# LICL_Amplifier.net
KiCad netlist of a schematic drawn in EAGLE
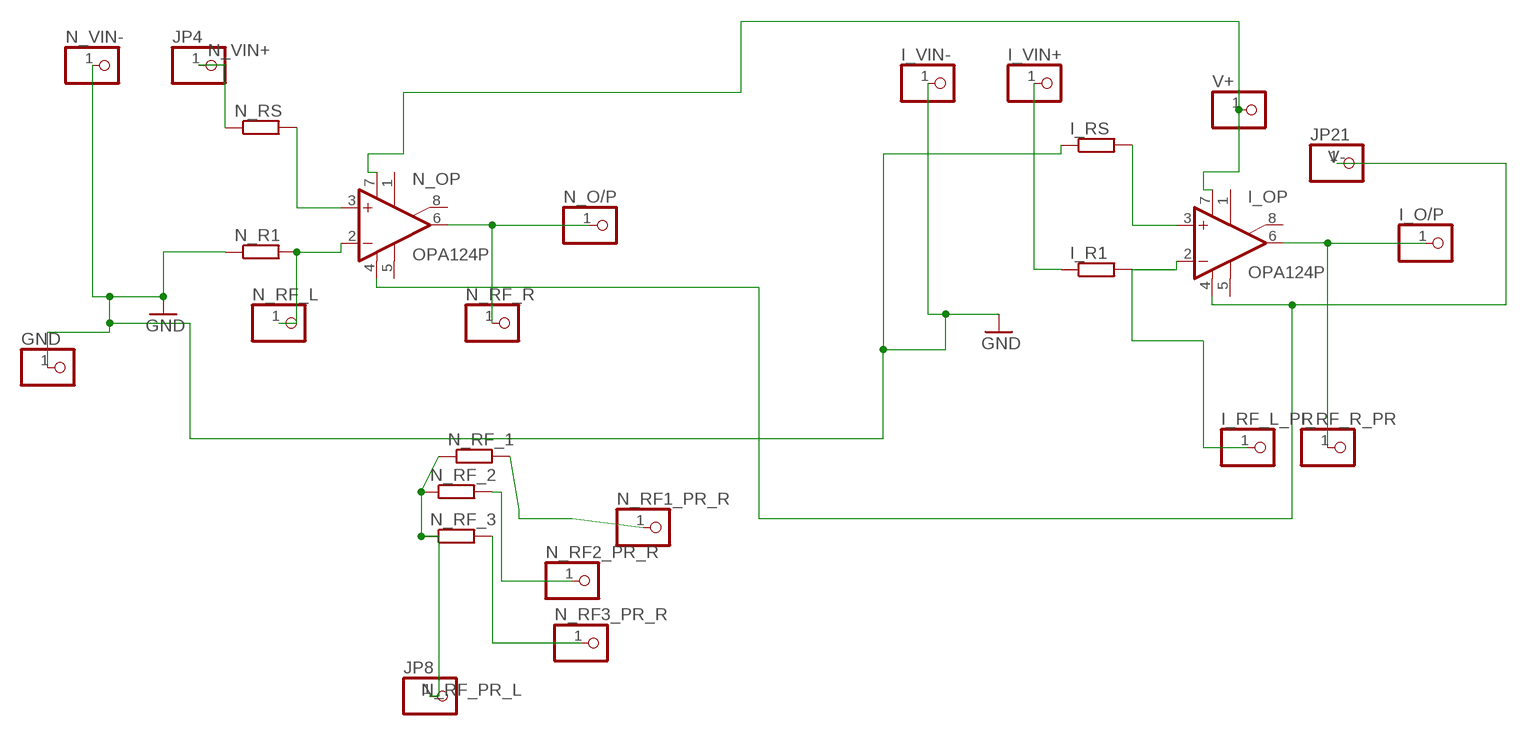
[diagram p0: schematic, sheet 1]

(export (version "E")
  (design (tool "Eeschema 10.0.6"))
  (components
    (comp (ref "GND")
      (value "PINHD-1X1")
      (footprint "eagle-import:1X01")
      (libsource (lib "eagle-import") (part "PINHD-1X1"))
    )
    (comp (ref "I_O/P")
      (value "PINHD-1X1")
      (footprint "eagle-import:1X01")
      (libsource (lib "eagle-import") (part "PINHD-1X1"))
    )
    (comp (ref "I_OP")
      (value "OPA124P")
      (footprint "eagle-import:DIL08")
      (libsource (lib "eagle-import") (part "OPA124P"))
    )
    (comp (ref "I_R1")
      (value "R-EU_0207/10")
      (footprint "eagle-import:0207_10")
      (libsource (lib "eagle-import") (part "R-EU_0207/10"))
    )
    (comp (ref "I_RF_L_PR")
      (value "PINHD-1X1")
      (footprint "eagle-import:1X01")
      (libsource (lib "eagle-import") (part "PINHD-1X1"))
    )
    (comp (ref "I_RF_R_PR")
      (value "PINHD-1X1")
      (footprint "eagle-import:1X01")
      (libsource (lib "eagle-import") (part "PINHD-1X1"))
    )
    (comp (ref "I_RS")
      (value "R-EU_0207/10")
      (footprint "eagle-import:0207_10")
      (libsource (lib "eagle-import") (part "R-EU_0207/10"))
    )
    (comp (ref "I_VIN+")
      (value "PINHD-1X1")
      (footprint "eagle-import:1X01")
      (libsource (lib "eagle-import") (part "PINHD-1X1"))
    )
    (comp (ref "I_VIN-")
      (value "PINHD-1X1")
      (footprint "eagle-import:1X01")
      (libsource (lib "eagle-import") (part "PINHD-1X1"))
    )
    (comp (ref "JP4")
      (value "PINHD-1X1")
      (footprint "eagle-import:1X01")
      (libsource (lib "eagle-import") (part "PINHD-1X1"))
    )
    (comp (ref "JP8")
      (value "PINHD-1X1")
      (footprint "eagle-import:1X01")
      (libsource (lib "eagle-import") (part "PINHD-1X1"))
    )
    (comp (ref "JP21")
      (value "PINHD-1X1")
      (footprint "eagle-import:1X01")
      (libsource (lib "eagle-import") (part "PINHD-1X1"))
    )
    (comp (ref "N_O/P")
      (value "PINHD-1X1")
      (footprint "eagle-import:1X01")
      (libsource (lib "eagle-import") (part "PINHD-1X1"))
    )
    (comp (ref "N_OP")
      (value "OPA124P")
      (footprint "eagle-import:DIL08")
      (libsource (lib "eagle-import") (part "OPA124P"))
    )
    (comp (ref "N_R1")
      (value "R-EU_0207/10")
      (footprint "eagle-import:0207_10")
      (libsource (lib "eagle-import") (part "R-EU_0207/10"))
    )
    (comp (ref "N_RF1_PR_R")
      (value "PINHD-1X1")
      (footprint "eagle-import:1X01")
      (libsource (lib "eagle-import") (part "PINHD-1X1"))
    )
    (comp (ref "N_RF2_PR_R")
      (value "PINHD-1X1")
      (footprint "eagle-import:1X01")
      (libsource (lib "eagle-import") (part "PINHD-1X1"))
    )
    (comp (ref "N_RF3_PR_R")
      (value "PINHD-1X1")
      (footprint "eagle-import:1X01")
      (libsource (lib "eagle-import") (part "PINHD-1X1"))
    )
    (comp (ref "N_RF_1")
      (value "R-EU_0207/10")
      (footprint "eagle-import:0207_10")
      (libsource (lib "eagle-import") (part "R-EU_0207/10"))
    )
    (comp (ref "N_RF_2")
      (value "R-EU_0207/10")
      (footprint "eagle-import:0207_10")
      (libsource (lib "eagle-import") (part "R-EU_0207/10"))
    )
    (comp (ref "N_RF_3")
      (value "R-EU_0207/10")
      (footprint "eagle-import:0207_10")
      (libsource (lib "eagle-import") (part "R-EU_0207/10"))
    )
    (comp (ref "N_RF_L")
      (value "PINHD-1X1")
      (footprint "eagle-import:1X01")
      (libsource (lib "eagle-import") (part "PINHD-1X1"))
    )
    (comp (ref "N_RF_R")
      (value "PINHD-1X1")
      (footprint "eagle-import:1X01")
      (libsource (lib "eagle-import") (part "PINHD-1X1"))
    )
    (comp (ref "N_RS")
      (value "R-EU_0207/10")
      (footprint "eagle-import:0207_10")
      (libsource (lib "eagle-import") (part "R-EU_0207/10"))
    )
    (comp (ref "N_VIN-")
      (value "PINHD-1X1")
      (footprint "eagle-import:1X01")
      (libsource (lib "eagle-import") (part "PINHD-1X1"))
    )
    (comp (ref "V+")
      (value "PINHD-1X1")
      (footprint "eagle-import:1X01")
      (libsource (lib "eagle-import") (part "PINHD-1X1"))
    )
  )
  (nets
    (net (code "1") (name "/N_RF_PR_L") (class "Default")
      (node (ref "JP8") (pin "1") (pinfunction "1_1") (pintype "passive"))
      (node (ref "N_RF_1") (pin "1") (pinfunction "1_1") (pintype "passive"))
      (node (ref "N_RF_2") (pin "1") (pinfunction "1_1") (pintype "passive"))
      (node (ref "N_RF_3") (pin "1") (pinfunction "1_1") (pintype "passive"))
    )
    (net (code "2") (name "/N_VIN+") (class "Default")
      (node (ref "JP4") (pin "1") (pinfunction "1_1") (pintype "passive"))
      (node (ref "N_RS") (pin "1") (pinfunction "1_1") (pintype "passive"))
    )
    (net (code "3") (name "/V-") (class "Default")
      (node (ref "I_OP") (pin "4") (pinfunction "V-_4") (pintype "power_in"))
      (node (ref "JP21") (pin "1") (pinfunction "1_1") (pintype "passive"))
      (node (ref "N_OP") (pin "4") (pinfunction "V-_4") (pintype "power_in"))
    )
    (net (code "4") (name "GND") (class "Default")
      (node (ref "GND") (pin "1") (pinfunction "1_1") (pintype "passive"))
      (node (ref "I_RS") (pin "1") (pinfunction "1_1") (pintype "passive"))
      (node (ref "I_VIN-") (pin "1") (pinfunction "1_1") (pintype "passive"))
      (node (ref "N_R1") (pin "1") (pinfunction "1_1") (pintype "passive"))
      (node (ref "N_VIN-") (pin "1") (pinfunction "1_1") (pintype "passive"))
    )
    (net (code "5") (name "Net-(I_OP-+IN)") (class "Default")
      (node (ref "I_OP") (pin "3") (pinfunction "+IN_3") (pintype "input"))
      (node (ref "I_RS") (pin "2") (pinfunction "2_2") (pintype "passive"))
    )
    (net (code "6") (name "Net-(I_OP--IN)") (class "Default")
      (node (ref "I_OP") (pin "2") (pinfunction "-IN_2") (pintype "input"))
      (node (ref "I_R1") (pin "2") (pinfunction "2_2") (pintype "passive"))
      (node (ref "I_RF_L_PR") (pin "1") (pinfunction "1_1") (pintype "passive"))
    )
    (net (code "7") (name "Net-(I_OP-OUT)") (class "Default")
      (node (ref "I_O/P") (pin "1") (pinfunction "1_1") (pintype "passive"))
      (node (ref "I_OP") (pin "6") (pinfunction "OUT_6") (pintype "output"))
      (node (ref "I_RF_R_PR") (pin "1") (pinfunction "1_1") (pintype "passive"))
    )
    (net (code "8") (name "Net-(I_OP-V+)") (class "Default")
      (node (ref "I_OP") (pin "7") (pinfunction "V+_7") (pintype "power_in"))
      (node (ref "N_OP") (pin "7") (pinfunction "V+_7") (pintype "power_in"))
      (node (ref "V+") (pin "1") (pinfunction "1_1") (pintype "passive"))
    )
    (net (code "9") (name "Net-(I_R1-Pad1)") (class "Default")
      (node (ref "I_R1") (pin "1") (pinfunction "1_1") (pintype "passive"))
      (node (ref "I_VIN+") (pin "1") (pinfunction "1_1") (pintype "passive"))
    )
    (net (code "10") (name "Net-(N_OP-+IN)") (class "Default")
      (node (ref "N_OP") (pin "3") (pinfunction "+IN_3") (pintype "input"))
      (node (ref "N_RS") (pin "2") (pinfunction "2_2") (pintype "passive"))
    )
    (net (code "11") (name "Net-(N_OP--IN)") (class "Default")
      (node (ref "N_OP") (pin "2") (pinfunction "-IN_2") (pintype "input"))
      (node (ref "N_R1") (pin "2") (pinfunction "2_2") (pintype "passive"))
      (node (ref "N_RF_L") (pin "1") (pinfunction "1_1") (pintype "passive"))
    )
    (net (code "12") (name "Net-(N_OP-OUT)") (class "Default")
      (node (ref "N_O/P") (pin "1") (pinfunction "1_1") (pintype "passive"))
      (node (ref "N_OP") (pin "6") (pinfunction "OUT_6") (pintype "output"))
      (node (ref "N_RF_R") (pin "1") (pinfunction "1_1") (pintype "passive"))
    )
    (net (code "13") (name "Net-(N_RF1_PR_R-Pad1)") (class "Default")
      (node (ref "N_RF1_PR_R") (pin "1") (pinfunction "1_1") (pintype "passive"))
      (node (ref "N_RF_1") (pin "2") (pinfunction "2_2") (pintype "passive"))
    )
    (net (code "14") (name "Net-(N_RF2_PR_R-Pad1)") (class "Default")
      (node (ref "N_RF2_PR_R") (pin "1") (pinfunction "1_1") (pintype "passive"))
      (node (ref "N_RF_2") (pin "2") (pinfunction "2_2") (pintype "passive"))
    )
    (net (code "15") (name "Net-(N_RF3_PR_R-Pad1)") (class "Default")
      (node (ref "N_RF3_PR_R") (pin "1") (pinfunction "1_1") (pintype "passive"))
      (node (ref "N_RF_3") (pin "2") (pinfunction "2_2") (pintype "passive"))
    )
    (net (code "16") (name "unconnected-(I_OP-SUBS-Pad8)") (class "Default")
      (node (ref "I_OP") (pin "8") (pinfunction "SUBS_8") (pintype "passive"))
    )
    (net (code "17") (name "unconnected-(I_OP-TRIM1-Pad1)") (class "Default")
      (node (ref "I_OP") (pin "1") (pinfunction "TRIM1_1") (pintype "passive"))
    )
    (net (code "18") (name "unconnected-(I_OP-TRIM2-Pad5)") (class "Default")
      (node (ref "I_OP") (pin "5") (pinfunction "TRIM2_5") (pintype "passive"))
    )
    (net (code "19") (name "unconnected-(N_OP-SUBS-Pad8)") (class "Default")
      (node (ref "N_OP") (pin "8") (pinfunction "SUBS_8") (pintype "passive"))
    )
    (net (code "20") (name "unconnected-(N_OP-TRIM1-Pad1)") (class "Default")
      (node (ref "N_OP") (pin "1") (pinfunction "TRIM1_1") (pintype "passive"))
    )
    (net (code "21") (name "unconnected-(N_OP-TRIM2-Pad5)") (class "Default")
      (node (ref "N_OP") (pin "5") (pinfunction "TRIM2_5") (pintype "passive"))
    )
  )
)
